# CiroAttuatore_V1.net
KiCad netlist of a schematic drawn in EAGLE
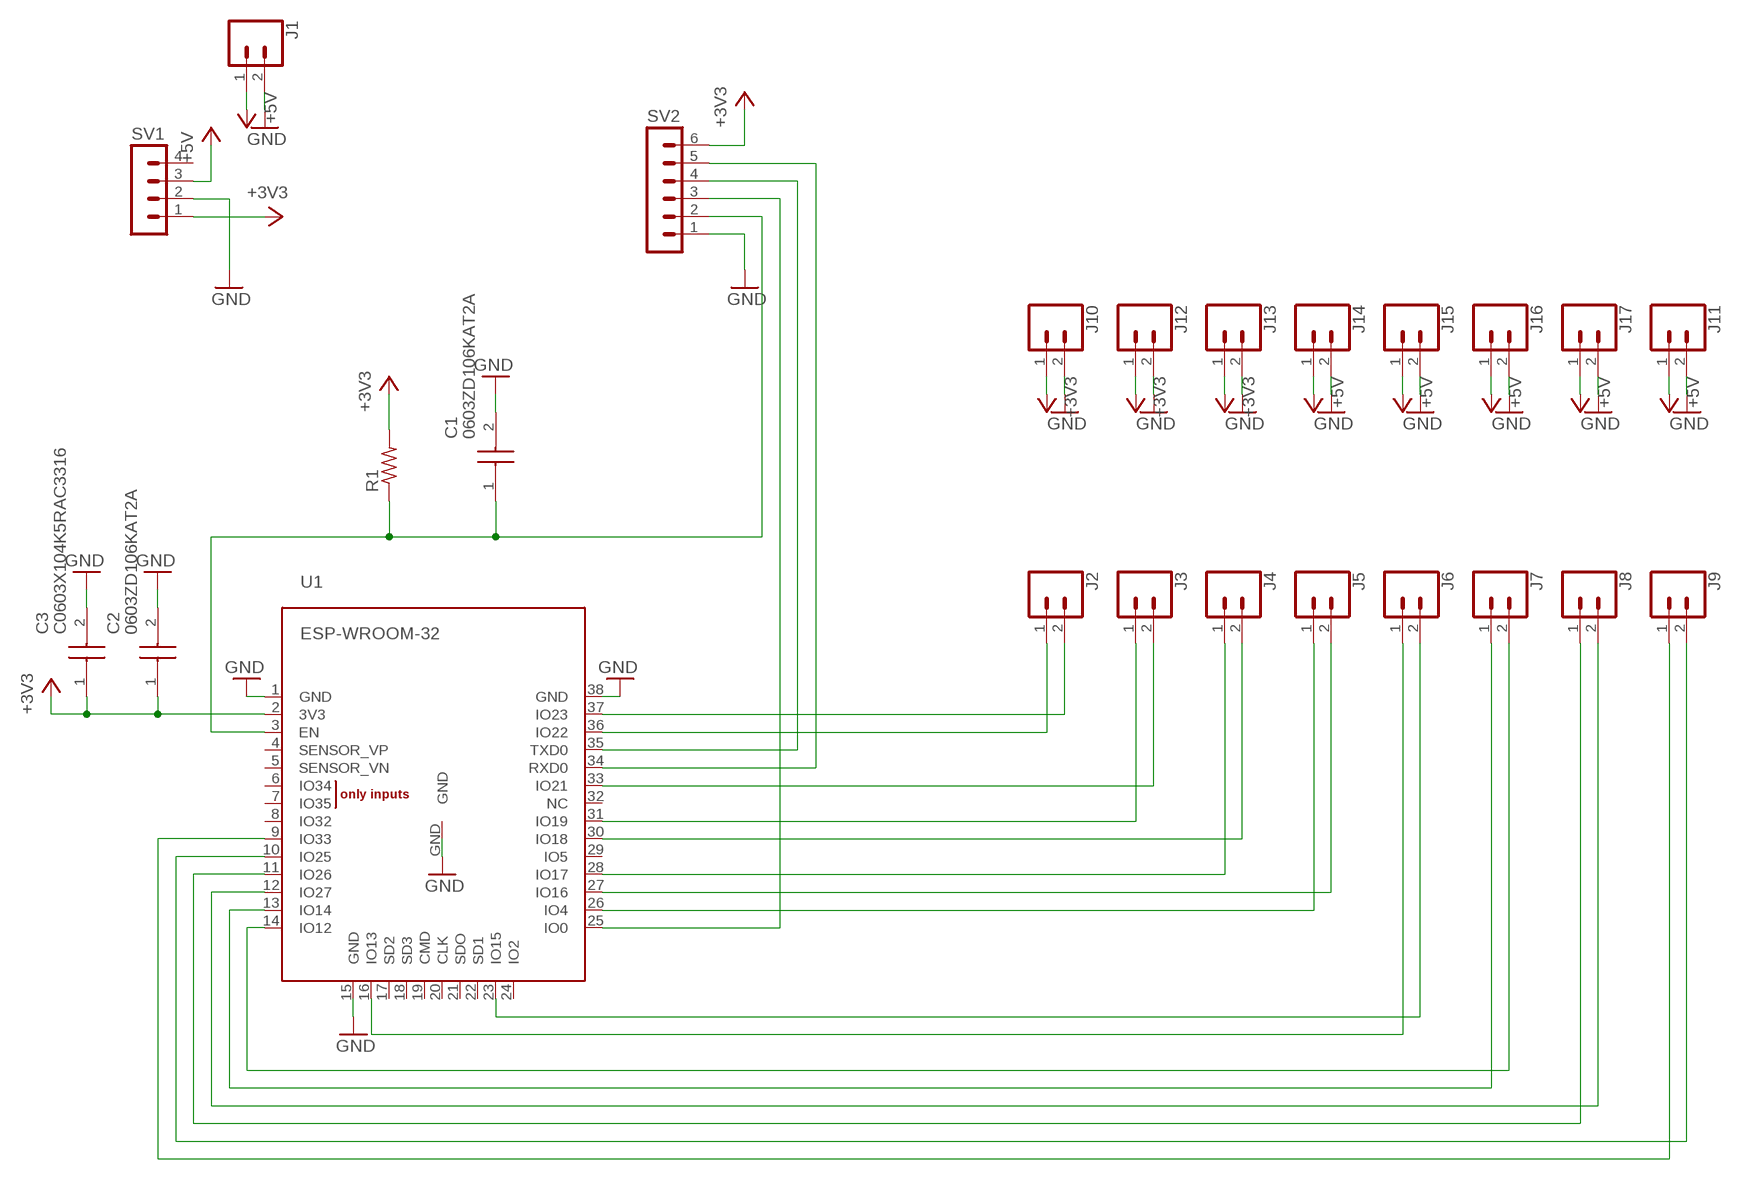
[diagram p0: schematic, sheet 1]

(export (version "E")
  (design (tool "Eeschema 10.0.6"))
  (components
    (comp (ref "C1")
      (value "0603ZD106KAT2A")
      (footprint "eagle-import:CAPC1608X90N")
      (fields (field (name "MOUSER_PART_NUMBER") "581-0603ZD106KAT2A"))
      (libsource (lib "eagle-import") (part "0603ZD106KAT2A"))
    )
    (comp (ref "C2")
      (value "0603ZD106KAT2A")
      (footprint "eagle-import:CAPC1608X90N")
      (fields (field (name "MOUSER_PART_NUMBER") "581-0603ZD106KAT2A"))
      (libsource (lib "eagle-import") (part "0603ZD106KAT2A"))
    )
    (comp (ref "C3")
      (value "C0603X104K5RAC3316")
      (footprint "eagle-import:CAPC1608X95N")
      (fields (field (name "MOUSER_PART_NUMBER") "80-C0603X104K5R3316"))
      (libsource (lib "eagle-import") (part "C0603X104K5RAC3316"))
    )
    (comp (ref "J1")
      (value "CONN_025MM")
      (footprint "eagle-import:SCREWTERMINAL-5MM-2")
      (libsource (lib "eagle-import") (part "CONN_025MM"))
    )
    (comp (ref "J2")
      (value "CONN_025MM")
      (footprint "eagle-import:SCREWTERMINAL-5MM-2")
      (libsource (lib "eagle-import") (part "CONN_025MM"))
    )
    (comp (ref "J3")
      (value "CONN_025MM")
      (footprint "eagle-import:SCREWTERMINAL-5MM-2")
      (libsource (lib "eagle-import") (part "CONN_025MM"))
    )
    (comp (ref "J4")
      (value "CONN_025MM")
      (footprint "eagle-import:SCREWTERMINAL-5MM-2")
      (libsource (lib "eagle-import") (part "CONN_025MM"))
    )
    (comp (ref "J5")
      (value "CONN_025MM")
      (footprint "eagle-import:SCREWTERMINAL-5MM-2")
      (libsource (lib "eagle-import") (part "CONN_025MM"))
    )
    (comp (ref "J6")
      (value "CONN_025MM")
      (footprint "eagle-import:SCREWTERMINAL-5MM-2")
      (libsource (lib "eagle-import") (part "CONN_025MM"))
    )
    (comp (ref "J7")
      (value "CONN_025MM")
      (footprint "eagle-import:SCREWTERMINAL-5MM-2")
      (libsource (lib "eagle-import") (part "CONN_025MM"))
    )
    (comp (ref "J8")
      (value "CONN_025MM")
      (footprint "eagle-import:SCREWTERMINAL-5MM-2")
      (libsource (lib "eagle-import") (part "CONN_025MM"))
    )
    (comp (ref "J9")
      (value "CONN_025MM")
      (footprint "eagle-import:SCREWTERMINAL-5MM-2")
      (libsource (lib "eagle-import") (part "CONN_025MM"))
    )
    (comp (ref "J10")
      (value "CONN_025MM")
      (footprint "eagle-import:SCREWTERMINAL-5MM-2")
      (libsource (lib "eagle-import") (part "CONN_025MM"))
    )
    (comp (ref "J11")
      (value "CONN_025MM")
      (footprint "eagle-import:SCREWTERMINAL-5MM-2")
      (libsource (lib "eagle-import") (part "CONN_025MM"))
    )
    (comp (ref "J12")
      (value "CONN_025MM")
      (footprint "eagle-import:SCREWTERMINAL-5MM-2")
      (libsource (lib "eagle-import") (part "CONN_025MM"))
    )
    (comp (ref "J13")
      (value "CONN_025MM")
      (footprint "eagle-import:SCREWTERMINAL-5MM-2")
      (libsource (lib "eagle-import") (part "CONN_025MM"))
    )
    (comp (ref "J14")
      (value "CONN_025MM")
      (footprint "eagle-import:SCREWTERMINAL-5MM-2")
      (libsource (lib "eagle-import") (part "CONN_025MM"))
    )
    (comp (ref "J15")
      (value "CONN_025MM")
      (footprint "eagle-import:SCREWTERMINAL-5MM-2")
      (libsource (lib "eagle-import") (part "CONN_025MM"))
    )
    (comp (ref "J16")
      (value "CONN_025MM")
      (footprint "eagle-import:SCREWTERMINAL-5MM-2")
      (libsource (lib "eagle-import") (part "CONN_025MM"))
    )
    (comp (ref "J17")
      (value "CONN_025MM")
      (footprint "eagle-import:SCREWTERMINAL-5MM-2")
      (libsource (lib "eagle-import") (part "CONN_025MM"))
    )
    (comp (ref "R1")
      (value "R-US_R0603")
      (footprint "eagle-import:R0603")
      (libsource (lib "eagle-import") (part "R-US_R0603"))
    )
    (comp (ref "SV1")
      (value "MA04-1")
      (footprint "eagle-import:MA04-1")
      (libsource (lib "eagle-import") (part "MA04-1"))
    )
    (comp (ref "SV2")
      (value "MA06-1")
      (footprint "eagle-import:MA06-1")
      (libsource (lib "eagle-import") (part "MA06-1"))
    )
    (comp (ref "U1")
      (value "ESP-WROOM-32")
      (footprint "eagle-import:ESP-WROOM-32")
      (libsource (lib "eagle-import") (part "ESP-WROOM-32"))
    )
  )
  (nets
    (net (code "1") (name "+3V3") (class "Default")
      (node (ref "C2") (pin "1") (pinfunction "1_1") (pintype "bidirectional"))
      (node (ref "C3") (pin "1") (pinfunction "1_1") (pintype "bidirectional"))
      (node (ref "J10") (pin "1") (pinfunction "1_1") (pintype "passive"))
      (node (ref "J12") (pin "1") (pinfunction "1_1") (pintype "passive"))
      (node (ref "J13") (pin "1") (pinfunction "1_1") (pintype "passive"))
      (node (ref "R1") (pin "2") (pinfunction "2_2") (pintype "passive"))
      (node (ref "SV1") (pin "1") (pinfunction "1_1") (pintype "passive"))
      (node (ref "SV2") (pin "6") (pinfunction "6_6") (pintype "passive"))
      (node (ref "U1") (pin "2") (pinfunction "3V3_2") (pintype "bidirectional"))
    )
    (net (code "2") (name "+5V") (class "Default")
      (node (ref "J1") (pin "1") (pinfunction "1_1") (pintype "passive"))
      (node (ref "J11") (pin "1") (pinfunction "1_1") (pintype "passive"))
      (node (ref "J14") (pin "1") (pinfunction "1_1") (pintype "passive"))
      (node (ref "J15") (pin "1") (pinfunction "1_1") (pintype "passive"))
      (node (ref "J16") (pin "1") (pinfunction "1_1") (pintype "passive"))
      (node (ref "J17") (pin "1") (pinfunction "1_1") (pintype "passive"))
      (node (ref "SV1") (pin "3") (pinfunction "3_3") (pintype "passive"))
    )
    (net (code "3") (name "GND") (class "Default")
      (node (ref "C1") (pin "2") (pinfunction "2_2") (pintype "bidirectional"))
      (node (ref "C2") (pin "2") (pinfunction "2_2") (pintype "bidirectional"))
      (node (ref "C3") (pin "2") (pinfunction "2_2") (pintype "bidirectional"))
      (node (ref "J1") (pin "2") (pinfunction "2_2") (pintype "passive"))
      (node (ref "J10") (pin "2") (pinfunction "2_2") (pintype "passive"))
      (node (ref "J11") (pin "2") (pinfunction "2_2") (pintype "passive"))
      (node (ref "J12") (pin "2") (pinfunction "2_2") (pintype "passive"))
      (node (ref "J13") (pin "2") (pinfunction "2_2") (pintype "passive"))
      (node (ref "J14") (pin "2") (pinfunction "2_2") (pintype "passive"))
      (node (ref "J15") (pin "2") (pinfunction "2_2") (pintype "passive"))
      (node (ref "J16") (pin "2") (pinfunction "2_2") (pintype "passive"))
      (node (ref "J17") (pin "2") (pinfunction "2_2") (pintype "passive"))
      (node (ref "SV1") (pin "2") (pinfunction "2_2") (pintype "passive"))
      (node (ref "SV2") (pin "1") (pinfunction "1_1") (pintype "passive"))
      (node (ref "U1") (pin "1") (pinfunction "GND_1") (pintype "bidirectional"))
      (node (ref "U1") (pin "15") (pinfunction "GND_15") (pintype "bidirectional"))
      (node (ref "U1") (pin "38") (pinfunction "GND_38") (pintype "bidirectional"))
      (node (ref "U1") (pin "GND") (pinfunction "GND_GND") (pintype "bidirectional"))
    )
    (net (code "4") (name "Net-(U1-EN)") (class "Default")
      (node (ref "C1") (pin "1") (pinfunction "1_1") (pintype "bidirectional"))
      (node (ref "R1") (pin "1") (pinfunction "1_1") (pintype "passive"))
      (node (ref "SV2") (pin "2") (pinfunction "2_2") (pintype "passive"))
      (node (ref "U1") (pin "3") (pinfunction "EN_3") (pintype "bidirectional"))
    )
    (net (code "5") (name "Net-(U1-IO0)") (class "Default")
      (node (ref "SV2") (pin "3") (pinfunction "3_3") (pintype "passive"))
      (node (ref "U1") (pin "25") (pinfunction "IO0_25") (pintype "bidirectional"))
    )
    (net (code "6") (name "Net-(U1-IO4)") (class "Default")
      (node (ref "J5") (pin "1") (pinfunction "1_1") (pintype "passive"))
      (node (ref "U1") (pin "26") (pinfunction "IO4_26") (pintype "bidirectional"))
    )
    (net (code "7") (name "Net-(U1-IO12)") (class "Default")
      (node (ref "J7") (pin "2") (pinfunction "2_2") (pintype "passive"))
      (node (ref "U1") (pin "14") (pinfunction "IO12_14") (pintype "bidirectional"))
    )
    (net (code "8") (name "Net-(U1-IO13)") (class "Default")
      (node (ref "J6") (pin "1") (pinfunction "1_1") (pintype "passive"))
      (node (ref "U1") (pin "16") (pinfunction "IO13_16") (pintype "bidirectional"))
    )
    (net (code "9") (name "Net-(U1-IO14)") (class "Default")
      (node (ref "J7") (pin "1") (pinfunction "1_1") (pintype "passive"))
      (node (ref "U1") (pin "13") (pinfunction "IO14_13") (pintype "bidirectional"))
    )
    (net (code "10") (name "Net-(U1-IO15)") (class "Default")
      (node (ref "J6") (pin "2") (pinfunction "2_2") (pintype "passive"))
      (node (ref "U1") (pin "23") (pinfunction "IO15_23") (pintype "bidirectional"))
    )
    (net (code "11") (name "Net-(U1-IO16)") (class "Default")
      (node (ref "J5") (pin "2") (pinfunction "2_2") (pintype "passive"))
      (node (ref "U1") (pin "27") (pinfunction "IO16_27") (pintype "bidirectional"))
    )
    (net (code "12") (name "Net-(U1-IO17)") (class "Default")
      (node (ref "J4") (pin "1") (pinfunction "1_1") (pintype "passive"))
      (node (ref "U1") (pin "28") (pinfunction "IO17_28") (pintype "bidirectional"))
    )
    (net (code "13") (name "Net-(U1-IO18)") (class "Default")
      (node (ref "J4") (pin "2") (pinfunction "2_2") (pintype "passive"))
      (node (ref "U1") (pin "30") (pinfunction "IO18_30") (pintype "bidirectional"))
    )
    (net (code "14") (name "Net-(U1-IO19)") (class "Default")
      (node (ref "J3") (pin "1") (pinfunction "1_1") (pintype "passive"))
      (node (ref "U1") (pin "31") (pinfunction "IO19_31") (pintype "bidirectional"))
    )
    (net (code "15") (name "Net-(U1-IO21)") (class "Default")
      (node (ref "J3") (pin "2") (pinfunction "2_2") (pintype "passive"))
      (node (ref "U1") (pin "33") (pinfunction "IO21_33") (pintype "bidirectional"))
    )
    (net (code "16") (name "Net-(U1-IO22)") (class "Default")
      (node (ref "J2") (pin "1") (pinfunction "1_1") (pintype "passive"))
      (node (ref "U1") (pin "36") (pinfunction "IO22_36") (pintype "bidirectional"))
    )
    (net (code "17") (name "Net-(U1-IO23)") (class "Default")
      (node (ref "J2") (pin "2") (pinfunction "2_2") (pintype "passive"))
      (node (ref "U1") (pin "37") (pinfunction "IO23_37") (pintype "bidirectional"))
    )
    (net (code "18") (name "Net-(U1-IO25)") (class "Default")
      (node (ref "J9") (pin "2") (pinfunction "2_2") (pintype "passive"))
      (node (ref "U1") (pin "10") (pinfunction "IO25_10") (pintype "bidirectional"))
    )
    (net (code "19") (name "Net-(U1-IO26)") (class "Default")
      (node (ref "J8") (pin "1") (pinfunction "1_1") (pintype "passive"))
      (node (ref "U1") (pin "11") (pinfunction "IO26_11") (pintype "bidirectional"))
    )
    (net (code "20") (name "Net-(U1-IO27)") (class "Default")
      (node (ref "J8") (pin "2") (pinfunction "2_2") (pintype "passive"))
      (node (ref "U1") (pin "12") (pinfunction "IO27_12") (pintype "bidirectional"))
    )
    (net (code "21") (name "Net-(U1-IO33)") (class "Default")
      (node (ref "J9") (pin "1") (pinfunction "1_1") (pintype "passive"))
      (node (ref "U1") (pin "9") (pinfunction "IO33_9") (pintype "bidirectional"))
    )
    (net (code "22") (name "Net-(U1-RXD0)") (class "Default")
      (node (ref "SV2") (pin "5") (pinfunction "5_5") (pintype "passive"))
      (node (ref "U1") (pin "34") (pinfunction "RXD0_34") (pintype "bidirectional"))
    )
    (net (code "23") (name "Net-(U1-TXD0)") (class "Default")
      (node (ref "SV2") (pin "4") (pinfunction "4_4") (pintype "passive"))
      (node (ref "U1") (pin "35") (pinfunction "TXD0_35") (pintype "bidirectional"))
    )
    (net (code "24") (name "unconnected-(SV1-Pad4)") (class "Default")
      (node (ref "SV1") (pin "4") (pinfunction "4_4") (pintype "passive"))
    )
    (net (code "25") (name "unconnected-(U1-CLK-Pad20)") (class "Default")
      (node (ref "U1") (pin "20") (pinfunction "CLK_20") (pintype "bidirectional"))
    )
    (net (code "26") (name "unconnected-(U1-CMD-Pad19)") (class "Default")
      (node (ref "U1") (pin "19") (pinfunction "CMD_19") (pintype "bidirectional"))
    )
    (net (code "27") (name "unconnected-(U1-IO2-Pad24)") (class "Default")
      (node (ref "U1") (pin "24") (pinfunction "IO2_24") (pintype "bidirectional"))
    )
    (net (code "28") (name "unconnected-(U1-IO5-Pad29)") (class "Default")
      (node (ref "U1") (pin "29") (pinfunction "IO5_29") (pintype "bidirectional"))
    )
    (net (code "29") (name "unconnected-(U1-IO32-Pad8)") (class "Default")
      (node (ref "U1") (pin "8") (pinfunction "IO32_8") (pintype "bidirectional"))
    )
    (net (code "30") (name "unconnected-(U1-IO34-Pad6)") (class "Default")
      (node (ref "U1") (pin "6") (pinfunction "IO34_6") (pintype "input"))
    )
    (net (code "31") (name "unconnected-(U1-IO35-Pad7)") (class "Default")
      (node (ref "U1") (pin "7") (pinfunction "IO35_7") (pintype "input"))
    )
    (net (code "32") (name "unconnected-(U1-NC-Pad32)") (class "Default")
      (node (ref "U1") (pin "32") (pinfunction "NC_32") (pintype "bidirectional"))
    )
    (net (code "33") (name "unconnected-(U1-SD1-Pad22)") (class "Default")
      (node (ref "U1") (pin "22") (pinfunction "SD1_22") (pintype "bidirectional"))
    )
    (net (code "34") (name "unconnected-(U1-SD2-Pad17)") (class "Default")
      (node (ref "U1") (pin "17") (pinfunction "SD2_17") (pintype "bidirectional"))
    )
    (net (code "35") (name "unconnected-(U1-SD3-Pad18)") (class "Default")
      (node (ref "U1") (pin "18") (pinfunction "SD3_18") (pintype "bidirectional"))
    )
    (net (code "36") (name "unconnected-(U1-SDO-Pad21)") (class "Default")
      (node (ref "U1") (pin "21") (pinfunction "SDO_21") (pintype "bidirectional"))
    )
    (net (code "37") (name "unconnected-(U1-SENSOR_VN-Pad5)") (class "Default")
      (node (ref "U1") (pin "5") (pinfunction "SENSOR_VN_5") (pintype "input"))
    )
    (net (code "38") (name "unconnected-(U1-SENSOR_VP-Pad4)") (class "Default")
      (node (ref "U1") (pin "4") (pinfunction "SENSOR_VP_4") (pintype "input"))
    )
  )
)
